# Powersupply.net
KiCad netlist of a schematic drawn in Altium Designer
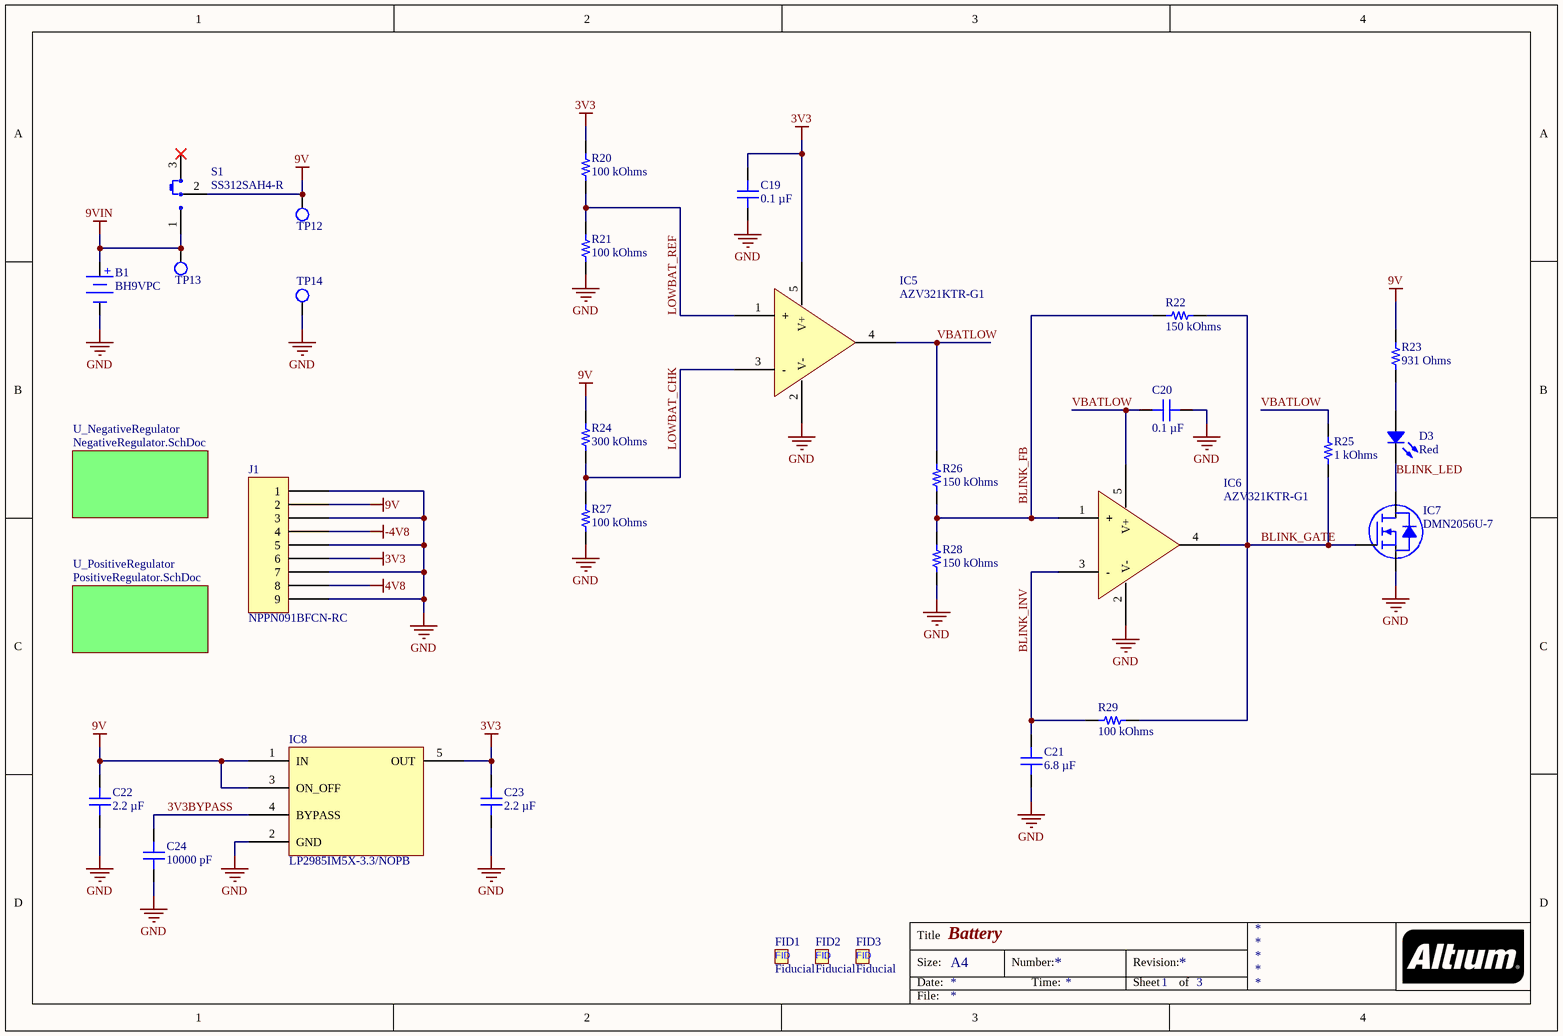
[diagram p0: Powersupply.SchDoc]

(export (version "E")
  (design (tool "Eeschema 10.0.6"))
  (components
    (comp (ref "B1")
      (value "BH9VPC")
      (footprint "MPD BH9VPC")
      (description "BATT HOLDER 9V 1 CELL PC PIN")
      (fields (field (name "MANUFACTURER") "MPD (Memory Protection Devices)"))
      (libsource (lib "altiumlibrary.com") (part "MPD BH9VPC"))
    )
    (comp (ref "C19")
      (value "0.1 µF")
      (footprint "CAP 0603_1608")
      (description "CAP CER 0.1UF 16V X7R 0603")
      (fields
        (field (name "PART NUMBER") "CL10B104KO8NNNC")
        (field (name "MANUFACTURER") "Samsung Electro-Mechanics")
      )
      (libsource (lib "altiumlibrary.com") (part "Capacitor"))
    )
    (comp (ref "C20")
      (value "0.1 µF")
      (footprint "CAP 0603_1608")
      (description "CAP CER 0.1UF 16V X7R 0603")
      (fields
        (field (name "PART NUMBER") "CL10B104KO8NNNC")
        (field (name "MANUFACTURER") "Samsung Electro-Mechanics")
      )
      (libsource (lib "altiumlibrary.com") (part "Capacitor"))
    )
    (comp (ref "C21")
      (value "6.8 µF")
      (footprint "CAP 0805_2012")
      (description "CAP CER 6.8UF 6.3V X7R 0805")
      (fields
        (field (name "PART NUMBER") "CGA4J1X7R0J685M125AC")
        (field (name "MANUFACTURER") "TDK Corporation")
      )
      (libsource (lib "altiumlibrary.com") (part "Capacitor"))
    )
    (comp (ref "C22")
      (value "2.2 µF")
      (footprint "CAP 0805_2012")
      (description "CAP CER 2.2UF 25V X7R 0805")
      (fields
        (field (name "PART NUMBER") "GRM21BR71E225KE11L")
        (field (name "MANUFACTURER") "Murata Electronics")
      )
      (libsource (lib "altiumlibrary.com") (part "Capacitor"))
    )
    (comp (ref "C23")
      (value "2.2 µF")
      (footprint "CAP 0805_2012")
      (description "CAP CER 2.2UF 25V X7R 0805")
      (fields
        (field (name "PART NUMBER") "GRM21BR71E225KE11L")
        (field (name "MANUFACTURER") "Murata Electronics")
      )
      (libsource (lib "altiumlibrary.com") (part "Capacitor"))
    )
    (comp (ref "C24")
      (value "10000 pF")
      (footprint "CAP 0603_1608")
      (description "CAP CER 10000PF 50V X7R 0603")
      (fields
        (field (name "PART NUMBER") "0603B103K500CT")
        (field (name "MANUFACTURER") "Walsin Technology Corporation")
      )
      (libsource (lib "altiumlibrary.com") (part "Capacitor"))
    )
    (comp (ref "D3")
      (value "Red")
      (footprint "LED 0805_2012 RED")
      (description "LED RED CLEAR CHIP SMD")
      (fields (field (name "PART NUMBER") "APT2012SURCK") (field (name "MANUFACTURER") "Kingbright"))
      (libsource (lib "altiumlibrary.com") (part "LED"))
    )
    (comp (ref "FID1")
      (value "Fiducial")
      (footprint "Fiducial-1mm")
      (libsource (lib "Original Circuit") (part "Fiducial"))
    )
    (comp (ref "FID2")
      (value "Fiducial")
      (footprint "Fiducial-1mm")
      (libsource (lib "Original Circuit") (part "Fiducial"))
    )
    (comp (ref "FID3")
      (value "Fiducial")
      (footprint "Fiducial-1mm")
      (libsource (lib "Original Circuit") (part "Fiducial"))
    )
    (comp (ref "IC5")
      (value "AZV321KTR-G1")
      (footprint "DIODES SOT-23-5 K")
      (description "IC OPAMP GP 1 CIRCUIT SOT23-5")
      (fields (field (name "MANUFACTURER") "Diodes Incorporated"))
      (libsource (lib "altiumlibrary.com") (part "DIODES AZV321"))
    )
    (comp (ref "IC6")
      (value "AZV321KTR-G1")
      (footprint "DIODES SOT-23-5 K")
      (description "IC OPAMP GP 1 CIRCUIT SOT23-5")
      (fields (field (name "MANUFACTURER") "Diodes Incorporated"))
      (libsource (lib "altiumlibrary.com") (part "DIODES AZV321"))
    )
    (comp (ref "IC7")
      (value "DMN2056U-7")
      (footprint "DIODES SOT-23-3")
      (description "MOSFET N-CHANNEL 20V 4A SOT23-3")
      (fields (field (name "MANUFACTURER") "Diodes Incorporated"))
      (libsource (lib "altiumlibrary.com") (part "DIODES INC MOSFET N-CH SOT-23-3"))
    )
    (comp (ref "IC8")
      (value "LP2985IM5X-3.3/NOPB")
      (footprint "TI SOT-23-5 DBV")
      (description "IC REG LINEAR 3.3V 150MA SOT23-5")
      (fields (field (name "MANUFACTURER") "Texas Instruments"))
      (libsource (lib "altiumlibrary.com") (part "TI LP2985-N DBV"))
    )
    (comp (ref "J1")
      (value "NPPN091BFCN-RC")
      (footprint "SULLINS NPPN091BFCN")
      (description "CONN HDR 9POS 0.079 GOLD PCB")
      (fields (field (name "MANUFACTURER") "Sullins Connector Solutions"))
      (libsource (lib "altiumlibrary.com") (part "9 Pin"))
    )
    (comp (ref "R20")
      (value "100 kOhms")
      (footprint "RES 0603_1608")
      (description "RES 100K OHM 0.1% 1/5W 0603")
      (fields
        (field (name "PART NUMBER") "RS73F1JTTD1003B")
        (field (name "MANUFACTURER") "KOA Speer Electronics, Inc.")
      )
      (libsource (lib "altiumlibrary.com") (part "Resistor"))
    )
    (comp (ref "R21")
      (value "100 kOhms")
      (footprint "RES 0603_1608")
      (description "RES 100K OHM 0.1% 1/5W 0603")
      (fields
        (field (name "PART NUMBER") "RS73F1JTTD1003B")
        (field (name "MANUFACTURER") "KOA Speer Electronics, Inc.")
      )
      (libsource (lib "altiumlibrary.com") (part "Resistor"))
    )
    (comp (ref "R22")
      (value "150 kOhms")
      (footprint "RES 0603_1608")
      (description "RES 150K OHM 1% 1/10W 0603")
      (fields
        (field (name "PART NUMBER") "RMCF0603FG150K")
        (field (name "MANUFACTURER") "Stackpole Electronics Inc")
      )
      (libsource (lib "altiumlibrary.com") (part "Resistor"))
    )
    (comp (ref "R23")
      (value "931 Ohms")
      (footprint "RES 0603_1608")
      (description "RES 931 OHM 1% 1/8W 0603")
      (fields
        (field (name "PART NUMBER") "RK73H1JTTD9310F")
        (field (name "MANUFACTURER") "KOA Speer Electronics, Inc.")
      )
      (libsource (lib "altiumlibrary.com") (part "Resistor"))
    )
    (comp (ref "R24")
      (value "300 kOhms")
      (footprint "RES 0603_1608")
      (description "RES 300K OHM 1% 1/10W 0603")
      (fields (field (name "PART NUMBER") "RC0603FR-07300KL") (field (name "MANUFACTURER") "Yageo"))
      (libsource (lib "altiumlibrary.com") (part "Resistor"))
    )
    (comp (ref "R25")
      (value "1 kOhms")
      (footprint "RES 0603_1608")
      (description "RES 1K OHM 1% 1/10W 0603")
      (fields
        (field (name "PART NUMBER") "RMCF0603FT1K00")
        (field (name "MANUFACTURER") "Stackpole Electronics Inc")
      )
      (libsource (lib "altiumlibrary.com") (part "Resistor"))
    )
    (comp (ref "R26")
      (value "150 kOhms")
      (footprint "RES 0603_1608")
      (description "RES 150K OHM 1% 1/10W 0603")
      (fields
        (field (name "PART NUMBER") "RMCF0603FG150K")
        (field (name "MANUFACTURER") "Stackpole Electronics Inc")
      )
      (libsource (lib "altiumlibrary.com") (part "Resistor"))
    )
    (comp (ref "R27")
      (value "100 kOhms")
      (footprint "RES 0603_1608")
      (description "RES 100K OHM 0.1% 1/5W 0603")
      (fields
        (field (name "PART NUMBER") "RS73F1JTTD1003B")
        (field (name "MANUFACTURER") "KOA Speer Electronics, Inc.")
      )
      (libsource (lib "altiumlibrary.com") (part "Resistor"))
    )
    (comp (ref "R28")
      (value "150 kOhms")
      (footprint "RES 0603_1608")
      (description "RES 150K OHM 1% 1/10W 0603")
      (fields
        (field (name "PART NUMBER") "RMCF0603FG150K")
        (field (name "MANUFACTURER") "Stackpole Electronics Inc")
      )
      (libsource (lib "altiumlibrary.com") (part "Resistor"))
    )
    (comp (ref "R29")
      (value "100 kOhms")
      (footprint "RES 0603_1608")
      (description "RES 100K OHM 0.1% 1/5W 0603")
      (fields
        (field (name "PART NUMBER") "RS73F1JTTD1003B")
        (field (name "MANUFACTURER") "KOA Speer Electronics, Inc.")
      )
      (libsource (lib "altiumlibrary.com") (part "Resistor"))
    )
    (comp (ref "S1")
      (value "SS312SAH4-R")
      (footprint "NKK SS312SAH4")
      (description "SWITCH SLIDE SPDT 0.4VA 28V")
      (fields (field (name "MANUFACTURER") "NKK Switches"))
      (libsource (lib "altiumlibrary.com") (part "NKK SS312"))
    )
    (comp (ref "TP12")
      (value "Test Point")
      (footprint "TestPoint-1.5mm")
      (libsource (lib "Original Circuit") (part "Test Point"))
    )
    (comp (ref "TP13")
      (value "Test Point")
      (footprint "TestPoint-1.5mm")
      (libsource (lib "Original Circuit") (part "Test Point"))
    )
    (comp (ref "TP14")
      (value "Test Point")
      (footprint "TestPoint-1.5mm")
      (libsource (lib "Original Circuit") (part "Test Point"))
    )
  )
  (nets
    (net (code "1") (name "-4V8") (class "Default")
      (node (ref "J1") (pin "4") (pinfunction "4_4") (pintype "passive"))
    )
    (net (code "2") (name "/3V3BYPASS") (class "Default")
      (node (ref "C24") (pin "2") (pinfunction "2_2") (pintype "passive"))
      (node (ref "IC8") (pin "4") (pinfunction "BYPASS_4") (pintype "passive"))
    )
    (net (code "3") (name "/BLINK_FB") (class "Default")
      (node (ref "IC6") (pin "1") (pinfunction "+_1") (pintype "passive"))
      (node (ref "R22") (pin "2") (pinfunction "2_2") (pintype "passive"))
      (node (ref "R26") (pin "1") (pinfunction "1_1") (pintype "passive"))
      (node (ref "R28") (pin "2") (pinfunction "2_2") (pintype "passive"))
    )
    (net (code "4") (name "/BLINK_GATE") (class "Default")
      (node (ref "IC6") (pin "4") (pinfunction "OUT_4") (pintype "passive"))
      (node (ref "IC7") (pin "1") (pinfunction "G_1") (pintype "passive"))
      (node (ref "R22") (pin "1") (pinfunction "1_1") (pintype "passive"))
      (node (ref "R25") (pin "1") (pinfunction "1_1") (pintype "passive"))
      (node (ref "R29") (pin "2") (pinfunction "2_2") (pintype "passive"))
    )
    (net (code "5") (name "/BLINK_INV") (class "Default")
      (node (ref "C21") (pin "2") (pinfunction "2_2") (pintype "passive"))
      (node (ref "IC6") (pin "3") (pinfunction "-_3") (pintype "passive"))
      (node (ref "R29") (pin "1") (pinfunction "1_1") (pintype "passive"))
    )
    (net (code "6") (name "/BLINK_LED") (class "Default")
      (node (ref "D3") (pin "2") (pinfunction "2_2") (pintype "passive"))
      (node (ref "IC7") (pin "3") (pinfunction "D_3") (pintype "passive"))
    )
    (net (code "7") (name "/LOWBAT_CHK") (class "Default")
      (node (ref "IC5") (pin "3") (pinfunction "-_3") (pintype "passive"))
      (node (ref "R24") (pin "1") (pinfunction "1_1") (pintype "passive"))
      (node (ref "R27") (pin "2") (pinfunction "2_2") (pintype "passive"))
    )
    (net (code "8") (name "/LOWBAT_REF") (class "Default")
      (node (ref "IC5") (pin "1") (pinfunction "+_1") (pintype "passive"))
      (node (ref "R20") (pin "1") (pinfunction "1_1") (pintype "passive"))
      (node (ref "R21") (pin "2") (pinfunction "2_2") (pintype "passive"))
    )
    (net (code "9") (name "/VBATLOW") (class "Default")
      (node (ref "C20") (pin "2") (pinfunction "2_2") (pintype "passive"))
      (node (ref "IC5") (pin "4") (pinfunction "OUT_4") (pintype "passive"))
      (node (ref "IC6") (pin "5") (pinfunction "V+_5") (pintype "passive"))
      (node (ref "R25") (pin "2") (pinfunction "2_2") (pintype "passive"))
      (node (ref "R26") (pin "2") (pinfunction "2_2") (pintype "passive"))
    )
    (net (code "10") (name "3V3") (class "Default")
      (node (ref "C19") (pin "2") (pinfunction "2_2") (pintype "passive"))
      (node (ref "C23") (pin "2") (pinfunction "2_2") (pintype "passive"))
      (node (ref "IC5") (pin "5") (pinfunction "V+_5") (pintype "passive"))
      (node (ref "IC8") (pin "5") (pinfunction "OUT_5") (pintype "passive"))
      (node (ref "J1") (pin "6") (pinfunction "6_6") (pintype "passive"))
      (node (ref "R20") (pin "2") (pinfunction "2_2") (pintype "passive"))
    )
    (net (code "11") (name "4V8") (class "Default")
      (node (ref "J1") (pin "8") (pinfunction "8_8") (pintype "passive"))
    )
    (net (code "12") (name "9V") (class "Default")
      (node (ref "C22") (pin "2") (pinfunction "2_2") (pintype "passive"))
      (node (ref "IC8") (pin "1") (pinfunction "IN_1") (pintype "passive"))
      (node (ref "IC8") (pin "3") (pinfunction "ON_OFF_3") (pintype "passive"))
      (node (ref "J1") (pin "2") (pinfunction "2_2") (pintype "passive"))
      (node (ref "R23") (pin "2") (pinfunction "2_2") (pintype "passive"))
      (node (ref "R24") (pin "2") (pinfunction "2_2") (pintype "passive"))
      (node (ref "S1") (pin "2") (pinfunction "COM_2") (pintype "passive"))
      (node (ref "TP12") (pin "1") (pinfunction "TP_1") (pintype "passive"))
    )
    (net (code "13") (name "9VIN") (class "Default")
      (node (ref "B1") (pin "1") (pinfunction "+_1") (pintype "passive"))
      (node (ref "S1") (pin "1") (pinfunction "1_1") (pintype "passive"))
      (node (ref "TP13") (pin "1") (pinfunction "TP_1") (pintype "passive"))
    )
    (net (code "14") (name "GND") (class "Default")
      (node (ref "B1") (pin "2") (pinfunction "-_2") (pintype "passive"))
      (node (ref "C19") (pin "1") (pinfunction "1_1") (pintype "passive"))
      (node (ref "C20") (pin "1") (pinfunction "1_1") (pintype "passive"))
      (node (ref "C21") (pin "1") (pinfunction "1_1") (pintype "passive"))
      (node (ref "C22") (pin "1") (pinfunction "1_1") (pintype "passive"))
      (node (ref "C23") (pin "1") (pinfunction "1_1") (pintype "passive"))
      (node (ref "C24") (pin "1") (pinfunction "1_1") (pintype "passive"))
      (node (ref "IC5") (pin "2") (pinfunction "V-_2") (pintype "passive"))
      (node (ref "IC6") (pin "2") (pinfunction "V-_2") (pintype "passive"))
      (node (ref "IC7") (pin "2") (pinfunction "S_2") (pintype "passive"))
      (node (ref "IC8") (pin "2") (pinfunction "GND_2") (pintype "passive"))
      (node (ref "J1") (pin "1") (pinfunction "1_1") (pintype "passive"))
      (node (ref "J1") (pin "3") (pinfunction "3_3") (pintype "passive"))
      (node (ref "J1") (pin "5") (pinfunction "5_5") (pintype "passive"))
      (node (ref "J1") (pin "7") (pinfunction "7_7") (pintype "passive"))
      (node (ref "J1") (pin "9") (pinfunction "9_9") (pintype "passive"))
      (node (ref "R21") (pin "1") (pinfunction "1_1") (pintype "passive"))
      (node (ref "R27") (pin "1") (pinfunction "1_1") (pintype "passive"))
      (node (ref "R28") (pin "1") (pinfunction "1_1") (pintype "passive"))
      (node (ref "TP14") (pin "1") (pinfunction "TP_1") (pintype "passive"))
    )
    (net (code "15") (name "Net-(D3-Pad1)") (class "Default")
      (node (ref "D3") (pin "1") (pinfunction "1_1") (pintype "passive"))
      (node (ref "R23") (pin "1") (pinfunction "1_1") (pintype "passive"))
    )
    (net (code "16") (name "unconnected-(S1-Pad3)") (class "Default")
      (node (ref "S1") (pin "3") (pinfunction "3_3") (pintype "passive+no_connect"))
    )
  )
)
